# Adafruit_DC_Stepper_Wing.net
KiCad netlist of a schematic drawn in EAGLE
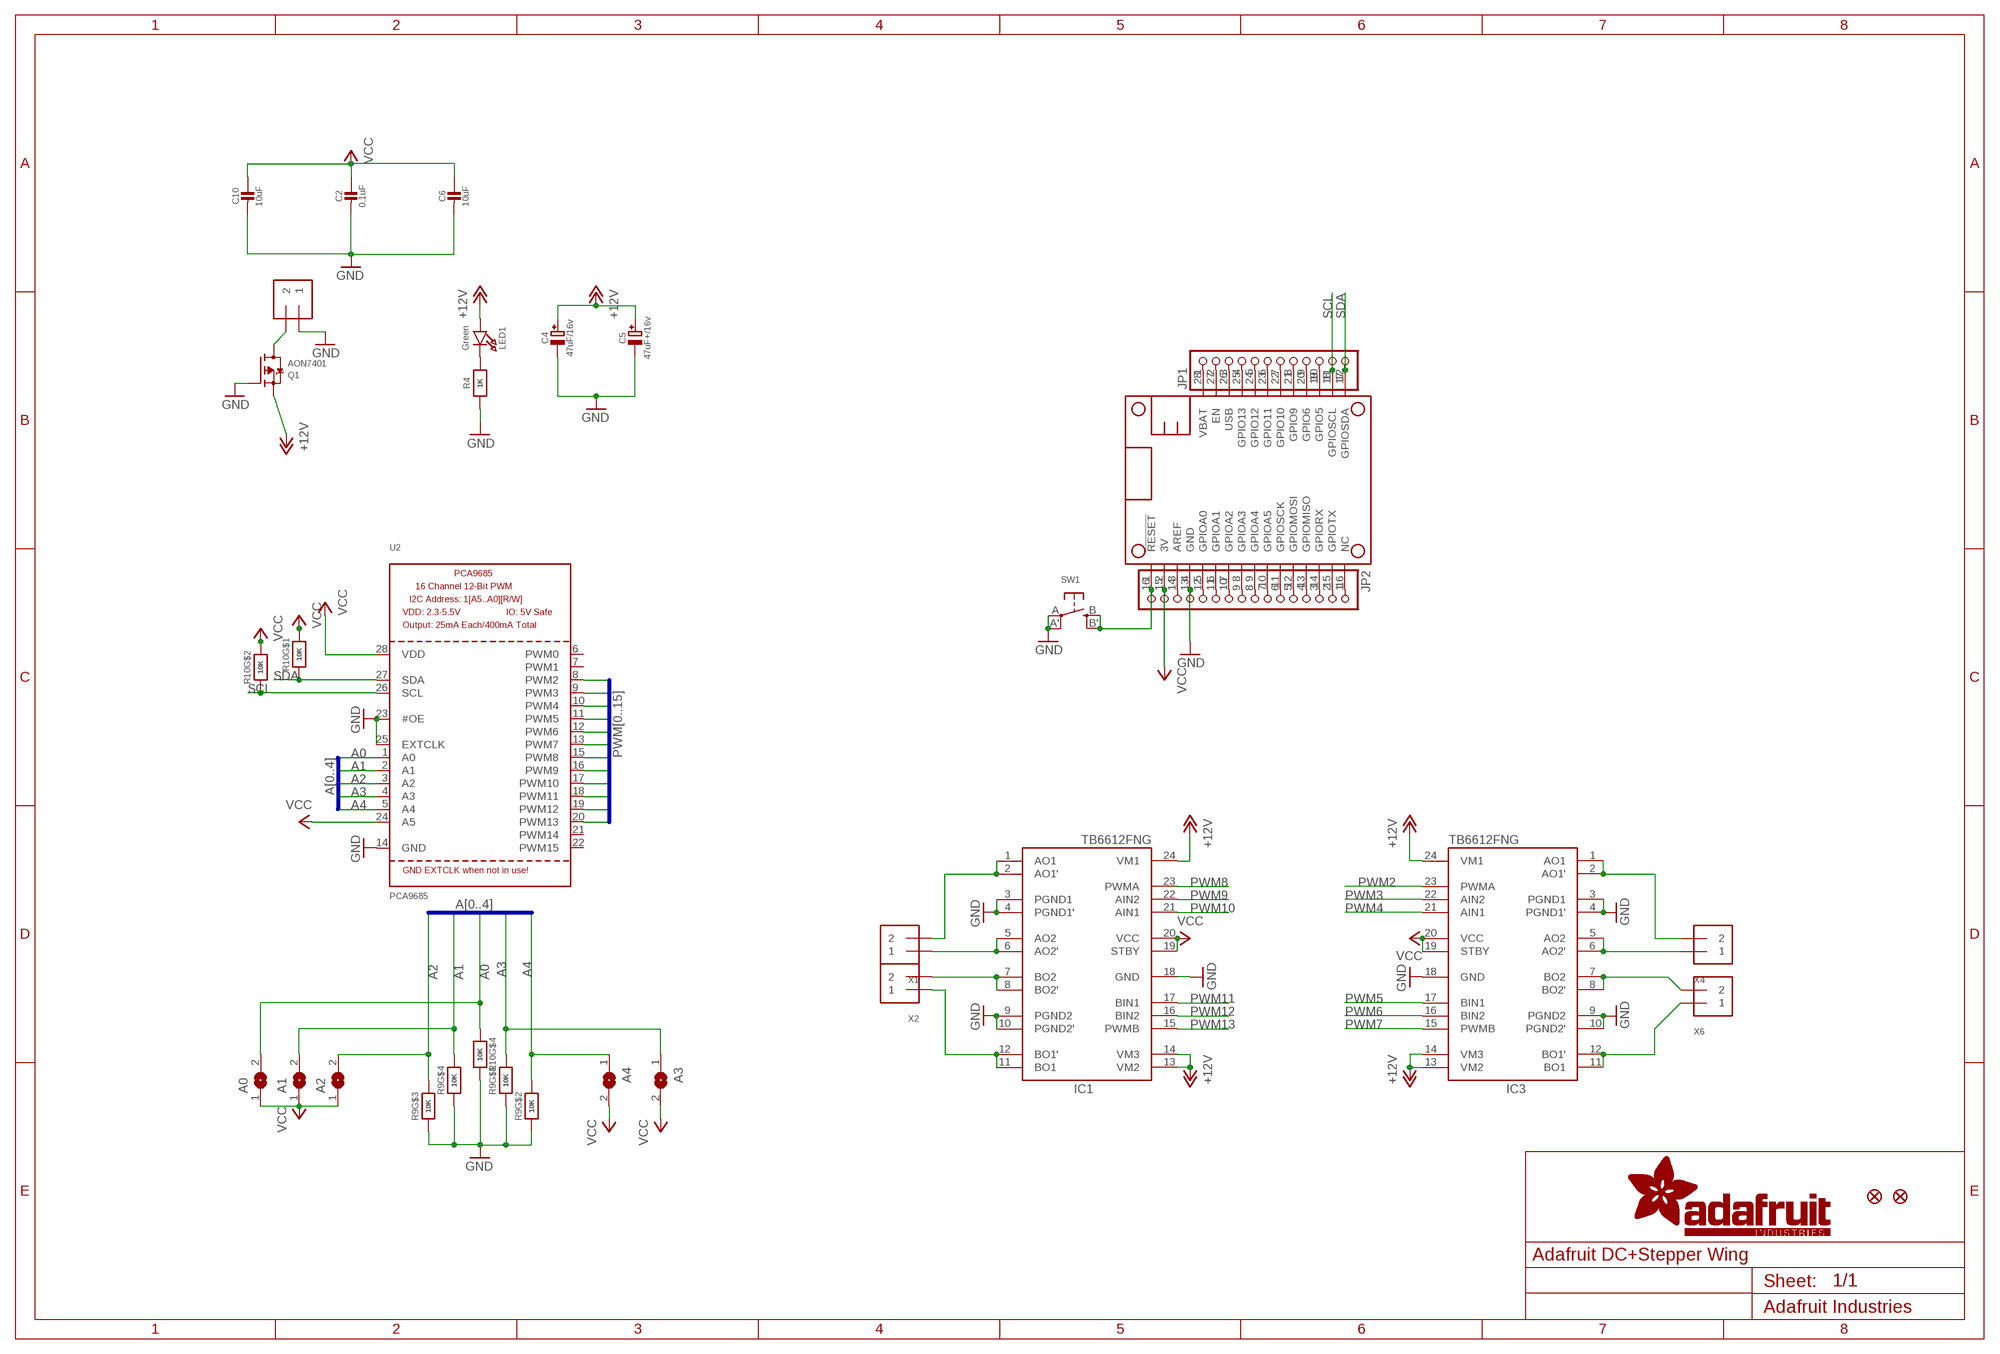
[diagram p0: schematic, sheet 1]

(export (version "E")
  (design (tool "Eeschema 10.0.6"))
  (components
    (comp (ref "A0")
      (value "SOLDERJUMPERREFLOW_NOPASTE")
      (footprint "eagle-import:SOLDERJUMPER_REFLOW_NOPASTE")
      (libsource (lib "eagle-import") (part "SOLDERJUMPERREFLOW_NOPASTE"))
    )
    (comp (ref "A1")
      (value "SOLDERJUMPERREFLOW_NOPASTE")
      (footprint "eagle-import:SOLDERJUMPER_REFLOW_NOPASTE")
      (libsource (lib "eagle-import") (part "SOLDERJUMPERREFLOW_NOPASTE"))
    )
    (comp (ref "A2")
      (value "SOLDERJUMPERREFLOW_NOPASTE")
      (footprint "eagle-import:SOLDERJUMPER_REFLOW_NOPASTE")
      (libsource (lib "eagle-import") (part "SOLDERJUMPERREFLOW_NOPASTE"))
    )
    (comp (ref "A3")
      (value "SOLDERJUMPERREFLOW_NOPASTE")
      (footprint "eagle-import:SOLDERJUMPER_REFLOW_NOPASTE")
      (libsource (lib "eagle-import") (part "SOLDERJUMPERREFLOW_NOPASTE"))
    )
    (comp (ref "A4")
      (value "SOLDERJUMPERREFLOW_NOPASTE")
      (footprint "eagle-import:SOLDERJUMPER_REFLOW_NOPASTE")
      (libsource (lib "eagle-import") (part "SOLDERJUMPERREFLOW_NOPASTE"))
    )
    (comp (ref "C2")
      (value "0.1uF")
      (footprint "eagle-import:0805-NO")
      (libsource (lib "eagle-import") (part "CAP_CERAMIC0805-NOOUTLINE"))
    )
    (comp (ref "C4")
      (value "47uF/16v")
      (footprint "eagle-import:PANASONIC_C")
      (libsource (lib "eagle-import") (part "CAP_ELECTROLYTICPANASONIC_C"))
    )
    (comp (ref "C5")
      (value "47uF+/16v")
      (footprint "eagle-import:PANASONIC_C")
      (libsource (lib "eagle-import") (part "CAP_ELECTROLYTICPANASONIC_C"))
    )
    (comp (ref "C6")
      (value "10uF")
      (footprint "eagle-import:0805-NO")
      (libsource (lib "eagle-import") (part "CAP_CERAMIC0805-NOOUTLINE"))
    )
    (comp (ref "C10")
      (value "10uF")
      (footprint "eagle-import:0805-NO")
      (libsource (lib "eagle-import") (part "CAP_CERAMIC0805-NOOUTLINE"))
    )
    (comp (ref "IC1")
      (value "TB6612FNG")
      (footprint "eagle-import:SSOP24")
      (libsource (lib "eagle-import") (part "TB6612FNG"))
    )
    (comp (ref "IC3")
      (value "TB6612FNG")
      (footprint "eagle-import:SSOP24")
      (libsource (lib "eagle-import") (part "TB6612FNG"))
    )
    (comp (ref "JP1")
      (value "HEADER-1X12")
      (footprint "eagle-import:1X12_ROUND")
      (libsource (lib "eagle-import") (part "HEADER-1X12"))
    )
    (comp (ref "JP2")
      (value "HEADER-1X16ROUND")
      (footprint "eagle-import:1X16_ROUND")
      (libsource (lib "eagle-import") (part "HEADER-1X16ROUND"))
    )
    (comp (ref "LED1")
      (value "Green")
      (footprint "eagle-import:CHIPLED_0805_NOOUTLINE")
      (libsource (lib "eagle-import") (part "LED0805_NOOUTLINE"))
    )
    (comp (ref "MPOWER")
      (value "1X2-3.5MM")
      (footprint "eagle-import:1X2-3.5MM")
      (libsource (lib "eagle-import") (part "1X2-3.5MM"))
    )
    (comp (ref "MS1")
      (value "FEATHERWING")
      (footprint "eagle-import:FEATHERWING")
      (libsource (lib "eagle-import") (part "FEATHERWING"))
    )
    (comp (ref "Q1")
      (value "AON7401")
      (footprint "eagle-import:POWERDI3333")
      (libsource (lib "eagle-import") (part "MOSFET-P-POWERDI3333"))
    )
    (comp (ref "R4")
      (value "1K")
      (footprint "eagle-import:0805-NO")
      (libsource (lib "eagle-import") (part "RESISTOR0805_NOOUTLINE"))
    )
    (comp (ref "R9")
      (value "10K")
      (footprint "eagle-import:RESPACK_4X0603")
      (libsource (lib "eagle-import") (part "RESISTOR_4PACK"))
    )
    (comp (ref "R10")
      (value "10K")
      (footprint "eagle-import:RESPACK_4X0603")
      (libsource (lib "eagle-import") (part "RESISTOR_4PACK"))
    )
    (comp (ref "SW1")
      (value "SWITCH_TACT_SMT4.6X2.8")
      (footprint "eagle-import:BTN_KMR2_4.6X2.8")
      (libsource (lib "eagle-import") (part "SWITCH_TACT_SMT4.6X2.8"))
    )
    (comp (ref "U$3")
      (value "FIDUCIAL\"\"")
      (footprint "eagle-import:FIDUCIAL_1MM")
      (libsource (lib "eagle-import") (part "FIDUCIAL{dblquote}{dblquote}"))
    )
    (comp (ref "U$4")
      (value "FIDUCIAL\"\"")
      (footprint "eagle-import:FIDUCIAL_1MM")
      (libsource (lib "eagle-import") (part "FIDUCIAL{dblquote}{dblquote}"))
    )
    (comp (ref "U2")
      (value "PCA9685")
      (footprint "eagle-import:TSSOP28")
      (libsource (lib "eagle-import") (part "PCA9685"))
    )
    (comp (ref "X1")
      (value "TERMBLOCK_1X2")
      (footprint "eagle-import:TERMBLOCK_1X2-3.5MM")
      (libsource (lib "eagle-import") (part "TERMBLOCK_1X2"))
    )
    (comp (ref "X2")
      (value "TERMBLOCK_1X2")
      (footprint "eagle-import:TERMBLOCK_1X2-3.5MM")
      (libsource (lib "eagle-import") (part "TERMBLOCK_1X2"))
    )
    (comp (ref "X4")
      (value "TERMBLOCK_1X2")
      (footprint "eagle-import:TERMBLOCK_1X2-3.5MM")
      (libsource (lib "eagle-import") (part "TERMBLOCK_1X2"))
    )
    (comp (ref "X6")
      (value "TERMBLOCK_1X2")
      (footprint "eagle-import:TERMBLOCK_1X2-3.5MM")
      (libsource (lib "eagle-import") (part "TERMBLOCK_1X2"))
    )
  )
  (nets
    (net (code "5") (name "+12V") (class "Default")
      (node (ref "C4") (pin "+") (pinfunction "+_+") (pintype "passive"))
      (node (ref "C5") (pin "+") (pinfunction "+_+") (pintype "passive"))
      (node (ref "IC1") (pin "13") (pinfunction "VM2_13") (pintype "power_in"))
      (node (ref "IC1") (pin "14") (pinfunction "VM3_14") (pintype "power_in"))
      (node (ref "IC1") (pin "24") (pinfunction "VM1_24") (pintype "power_in"))
      (node (ref "IC3") (pin "13") (pinfunction "VM2_13") (pintype "power_in"))
      (node (ref "IC3") (pin "14") (pinfunction "VM3_14") (pintype "power_in"))
      (node (ref "IC3") (pin "24") (pinfunction "VM1_24") (pintype "power_in"))
      (node (ref "LED1") (pin "A") (pinfunction "A_A") (pintype "passive"))
      (node (ref "Q1") (pin "1") (pinfunction "S_1") (pintype "passive"))
      (node (ref "Q1") (pin "2") (pinfunction "S_2") (pintype "passive"))
      (node (ref "Q1") (pin "3") (pinfunction "S_3") (pintype "passive"))
    )
    (net (code "6") (name "/A0") (class "Default")
      (node (ref "A0") (pin "2") (pinfunction "2_2") (pintype "passive"))
      (node (ref "R10") (pin "4") (pinfunction "1_4") (pintype "passive"))
      (node (ref "U2") (pin "1") (pinfunction "A0_1") (pintype "bidirectional"))
    )
    (net (code "7") (name "/A1") (class "Default")
      (node (ref "A1") (pin "2") (pinfunction "2_2") (pintype "passive"))
      (node (ref "R9") (pin "5") (pinfunction "2_5") (pintype "passive"))
      (node (ref "U2") (pin "2") (pinfunction "A1_2") (pintype "bidirectional"))
    )
    (net (code "8") (name "/A2") (class "Default")
      (node (ref "A2") (pin "2") (pinfunction "2_2") (pintype "passive"))
      (node (ref "R9") (pin "6") (pinfunction "2_6") (pintype "passive"))
      (node (ref "U2") (pin "3") (pinfunction "A2_3") (pintype "bidirectional"))
    )
    (net (code "9") (name "/A3") (class "Default")
      (node (ref "A3") (pin "1") (pinfunction "1_1") (pintype "passive"))
      (node (ref "R9") (pin "8") (pinfunction "2_8") (pintype "passive"))
      (node (ref "U2") (pin "4") (pinfunction "A3_4") (pintype "bidirectional"))
    )
    (net (code "10") (name "/A4") (class "Default")
      (node (ref "A4") (pin "1") (pinfunction "1_1") (pintype "passive"))
      (node (ref "R9") (pin "7") (pinfunction "2_7") (pintype "passive"))
      (node (ref "U2") (pin "5") (pinfunction "A4_5") (pintype "bidirectional"))
    )
    (net (code "12") (name "/PWM2") (class "Default")
      (node (ref "IC3") (pin "23") (pinfunction "PWMA_23") (pintype "input"))
      (node (ref "U2") (pin "8") (pinfunction "PWM2_8") (pintype "output"))
    )
    (net (code "13") (name "/PWM3") (class "Default")
      (node (ref "IC3") (pin "22") (pinfunction "AIN2_22") (pintype "input"))
      (node (ref "U2") (pin "9") (pinfunction "PWM3_9") (pintype "output"))
    )
    (net (code "14") (name "/PWM4") (class "Default")
      (node (ref "IC3") (pin "21") (pinfunction "AIN1_21") (pintype "input"))
      (node (ref "U2") (pin "10") (pinfunction "PWM4_10") (pintype "output"))
    )
    (net (code "15") (name "/PWM5") (class "Default")
      (node (ref "IC3") (pin "17") (pinfunction "BIN1_17") (pintype "input"))
      (node (ref "U2") (pin "11") (pinfunction "PWM5_11") (pintype "output"))
    )
    (net (code "16") (name "/PWM6") (class "Default")
      (node (ref "IC3") (pin "16") (pinfunction "BIN2_16") (pintype "input"))
      (node (ref "U2") (pin "12") (pinfunction "PWM6_12") (pintype "output"))
    )
    (net (code "17") (name "/PWM7") (class "Default")
      (node (ref "IC3") (pin "15") (pinfunction "PWMB_15") (pintype "input"))
      (node (ref "U2") (pin "13") (pinfunction "PWM7_13") (pintype "output"))
    )
    (net (code "18") (name "/PWM8") (class "Default")
      (node (ref "IC1") (pin "23") (pinfunction "PWMA_23") (pintype "input"))
      (node (ref "U2") (pin "15") (pinfunction "PWM8_15") (pintype "output"))
    )
    (net (code "19") (name "/PWM9") (class "Default")
      (node (ref "IC1") (pin "22") (pinfunction "AIN2_22") (pintype "input"))
      (node (ref "U2") (pin "16") (pinfunction "PWM9_16") (pintype "output"))
    )
    (net (code "20") (name "/PWM10") (class "Default")
      (node (ref "IC1") (pin "21") (pinfunction "AIN1_21") (pintype "input"))
      (node (ref "U2") (pin "17") (pinfunction "PWM10_17") (pintype "output"))
    )
    (net (code "21") (name "/PWM11") (class "Default")
      (node (ref "IC1") (pin "17") (pinfunction "BIN1_17") (pintype "input"))
      (node (ref "U2") (pin "18") (pinfunction "PWM11_18") (pintype "output"))
    )
    (net (code "22") (name "/PWM12") (class "Default")
      (node (ref "IC1") (pin "16") (pinfunction "BIN2_16") (pintype "input"))
      (node (ref "U2") (pin "19") (pinfunction "PWM12_19") (pintype "output"))
    )
    (net (code "23") (name "/PWM13") (class "Default")
      (node (ref "IC1") (pin "15") (pinfunction "PWMB_15") (pintype "input"))
      (node (ref "U2") (pin "20") (pinfunction "PWM13_20") (pintype "output"))
    )
    (net (code "25") (name "/SCL") (class "Default")
      (node (ref "JP1") (pin "11") (pinfunction "11_11") (pintype "passive"))
      (node (ref "MS1") (pin "18") (pinfunction "GPIOSCL_18") (pintype "bidirectional"))
      (node (ref "R10") (pin "2") (pinfunction "1_2") (pintype "passive"))
      (node (ref "U2") (pin "26") (pinfunction "SCL_26") (pintype "bidirectional"))
    )
    (net (code "26") (name "/SDA") (class "Default")
      (node (ref "JP1") (pin "12") (pinfunction "12_12") (pintype "passive"))
      (node (ref "MS1") (pin "17") (pinfunction "GPIOSDA_17") (pintype "bidirectional"))
      (node (ref "R10") (pin "1") (pinfunction "1_1") (pintype "passive"))
      (node (ref "U2") (pin "27") (pinfunction "SDA_27") (pintype "bidirectional"))
    )
    (net (code "27") (name "GND") (class "Default")
      (node (ref "C10") (pin "2") (pinfunction "2_2") (pintype "passive"))
      (node (ref "C2") (pin "2") (pinfunction "2_2") (pintype "passive"))
      (node (ref "C4") (pin "-") (pinfunction "-_-") (pintype "passive"))
      (node (ref "C5") (pin "-") (pinfunction "-_-") (pintype "passive"))
      (node (ref "C6") (pin "2") (pinfunction "2_2") (pintype "passive"))
      (node (ref "IC1") (pin "10") (pinfunction "PGND2'_10") (pintype "power_in"))
      (node (ref "IC1") (pin "18") (pinfunction "GND_18") (pintype "power_in"))
      (node (ref "IC1") (pin "3") (pinfunction "PGND1_3") (pintype "power_in"))
      (node (ref "IC1") (pin "4") (pinfunction "PGND1'_4") (pintype "power_in"))
      (node (ref "IC1") (pin "9") (pinfunction "PGND2_9") (pintype "power_in"))
      (node (ref "IC3") (pin "10") (pinfunction "PGND2'_10") (pintype "power_in"))
      (node (ref "IC3") (pin "18") (pinfunction "GND_18") (pintype "power_in"))
      (node (ref "IC3") (pin "3") (pinfunction "PGND1_3") (pintype "power_in"))
      (node (ref "IC3") (pin "4") (pinfunction "PGND1'_4") (pintype "power_in"))
      (node (ref "IC3") (pin "9") (pinfunction "PGND2_9") (pintype "power_in"))
      (node (ref "JP2") (pin "13") (pinfunction "13_13") (pintype "passive"))
      (node (ref "MPOWER") (pin "1") (pinfunction "1_1") (pintype "passive"))
      (node (ref "MS1") (pin "4") (pinfunction "GND_4") (pintype "power_in"))
      (node (ref "Q1") (pin "4") (pinfunction "G_4") (pintype "passive"))
      (node (ref "R10") (pin "5") (pinfunction "2_5") (pintype "passive"))
      (node (ref "R4") (pin "1") (pinfunction "1_1") (pintype "passive"))
      (node (ref "R9") (pin "1") (pinfunction "1_1") (pintype "passive"))
      (node (ref "R9") (pin "2") (pinfunction "1_2") (pintype "passive"))
      (node (ref "R9") (pin "3") (pinfunction "1_3") (pintype "passive"))
      (node (ref "R9") (pin "4") (pinfunction "1_4") (pintype "passive"))
      (node (ref "SW1") (pin "A") (pinfunction "P_A") (pintype "passive"))
      (node (ref "SW1") (pin "A'") (pinfunction "P1_A'") (pintype "passive"))
      (node (ref "U2") (pin "14") (pinfunction "GND_14") (pintype "power_in"))
      (node (ref "U2") (pin "23") (pinfunction "#OE_23") (pintype "input"))
      (node (ref "U2") (pin "25") (pinfunction "EXTCLK_25") (pintype "input"))
    )
    (net (code "28") (name "Net-(IC1-AO1')") (class "Default")
      (node (ref "IC1") (pin "1") (pinfunction "AO1_1") (pintype "output"))
      (node (ref "IC1") (pin "2") (pinfunction "AO1'_2") (pintype "output"))
      (node (ref "X1") (pin "2") (pinfunction "2_2") (pintype "passive"))
    )
    (net (code "29") (name "Net-(IC1-AO2')") (class "Default")
      (node (ref "IC1") (pin "5") (pinfunction "AO2_5") (pintype "output"))
      (node (ref "IC1") (pin "6") (pinfunction "AO2'_6") (pintype "output"))
      (node (ref "X1") (pin "1") (pinfunction "1_1") (pintype "passive"))
    )
    (net (code "30") (name "Net-(IC1-BO1')") (class "Default")
      (node (ref "IC1") (pin "11") (pinfunction "BO1_11") (pintype "output"))
      (node (ref "IC1") (pin "12") (pinfunction "BO1'_12") (pintype "output"))
      (node (ref "X2") (pin "1") (pinfunction "1_1") (pintype "passive"))
    )
    (net (code "31") (name "Net-(IC1-BO2')") (class "Default")
      (node (ref "IC1") (pin "7") (pinfunction "BO2_7") (pintype "output"))
      (node (ref "IC1") (pin "8") (pinfunction "BO2'_8") (pintype "output"))
      (node (ref "X2") (pin "2") (pinfunction "2_2") (pintype "passive"))
    )
    (net (code "32") (name "Net-(IC3-AO1')") (class "Default")
      (node (ref "IC3") (pin "1") (pinfunction "AO1_1") (pintype "output"))
      (node (ref "IC3") (pin "2") (pinfunction "AO1'_2") (pintype "output"))
      (node (ref "X4") (pin "2") (pinfunction "2_2") (pintype "passive"))
    )
    (net (code "33") (name "Net-(IC3-AO2')") (class "Default")
      (node (ref "IC3") (pin "5") (pinfunction "AO2_5") (pintype "output"))
      (node (ref "IC3") (pin "6") (pinfunction "AO2'_6") (pintype "output"))
      (node (ref "X4") (pin "1") (pinfunction "1_1") (pintype "passive"))
    )
    (net (code "34") (name "Net-(IC3-BO1')") (class "Default")
      (node (ref "IC3") (pin "11") (pinfunction "BO1_11") (pintype "output"))
      (node (ref "IC3") (pin "12") (pinfunction "BO1'_12") (pintype "output"))
      (node (ref "X6") (pin "1") (pinfunction "1_1") (pintype "passive"))
    )
    (net (code "35") (name "Net-(IC3-BO2')") (class "Default")
      (node (ref "IC3") (pin "7") (pinfunction "BO2_7") (pintype "output"))
      (node (ref "IC3") (pin "8") (pinfunction "BO2'_8") (pintype "output"))
      (node (ref "X6") (pin "2") (pinfunction "2_2") (pintype "passive"))
    )
    (net (code "36") (name "Net-(LED1-PadC)") (class "Default")
      (node (ref "LED1") (pin "C") (pinfunction "C_C") (pintype "passive"))
      (node (ref "R4") (pin "2") (pinfunction "2_2") (pintype "passive"))
    )
    (net (code "37") (name "Net-(MS1-AREF)") (class "Default")
      (node (ref "JP2") (pin "14") (pinfunction "14_14") (pintype "passive"))
      (node (ref "MS1") (pin "3") (pinfunction "AREF_3") (pintype "passive"))
    )
    (net (code "38") (name "Net-(MS1-EN)") (class "Default")
      (node (ref "JP1") (pin "2") (pinfunction "2_2") (pintype "passive"))
      (node (ref "MS1") (pin "27") (pinfunction "EN_27") (pintype "passive"))
    )
    (net (code "39") (name "Net-(MS1-GPIO5)") (class "Default")
      (node (ref "JP1") (pin "10") (pinfunction "10_10") (pintype "passive"))
      (node (ref "MS1") (pin "19") (pinfunction "GPIO5_19") (pintype "bidirectional"))
    )
    (net (code "40") (name "Net-(MS1-GPIO6)") (class "Default")
      (node (ref "JP1") (pin "9") (pinfunction "9_9") (pintype "passive"))
      (node (ref "MS1") (pin "20") (pinfunction "GPIO6_20") (pintype "bidirectional"))
    )
    (net (code "41") (name "Net-(MS1-GPIO9)") (class "Default")
      (node (ref "JP1") (pin "8") (pinfunction "8_8") (pintype "passive"))
      (node (ref "MS1") (pin "21") (pinfunction "GPIO9_21") (pintype "bidirectional"))
    )
    (net (code "42") (name "Net-(MS1-GPIO10)") (class "Default")
      (node (ref "JP1") (pin "7") (pinfunction "7_7") (pintype "passive"))
      (node (ref "MS1") (pin "22") (pinfunction "GPIO10_22") (pintype "bidirectional"))
    )
    (net (code "43") (name "Net-(MS1-GPIO11)") (class "Default")
      (node (ref "JP1") (pin "6") (pinfunction "6_6") (pintype "passive"))
      (node (ref "MS1") (pin "23") (pinfunction "GPIO11_23") (pintype "bidirectional"))
    )
    (net (code "44") (name "Net-(MS1-GPIO12)") (class "Default")
      (node (ref "JP1") (pin "5") (pinfunction "5_5") (pintype "passive"))
      (node (ref "MS1") (pin "24") (pinfunction "GPIO12_24") (pintype "bidirectional"))
    )
    (net (code "45") (name "Net-(MS1-GPIO13)") (class "Default")
      (node (ref "JP1") (pin "4") (pinfunction "4_4") (pintype "passive"))
      (node (ref "MS1") (pin "25") (pinfunction "GPIO13_25") (pintype "bidirectional"))
    )
    (net (code "46") (name "Net-(MS1-GPIOA0)") (class "Default")
      (node (ref "JP2") (pin "12") (pinfunction "12_12") (pintype "passive"))
      (node (ref "MS1") (pin "5") (pinfunction "GPIOA0_5") (pintype "bidirectional"))
    )
    (net (code "47") (name "Net-(MS1-GPIOA1)") (class "Default")
      (node (ref "JP2") (pin "11") (pinfunction "11_11") (pintype "passive"))
      (node (ref "MS1") (pin "6") (pinfunction "GPIOA1_6") (pintype "bidirectional"))
    )
    (net (code "48") (name "Net-(MS1-GPIOA2)") (class "Default")
      (node (ref "JP2") (pin "10") (pinfunction "10_10") (pintype "passive"))
      (node (ref "MS1") (pin "7") (pinfunction "GPIOA2_7") (pintype "bidirectional"))
    )
    (net (code "49") (name "Net-(MS1-GPIOA3)") (class "Default")
      (node (ref "JP2") (pin "9") (pinfunction "9_9") (pintype "passive"))
      (node (ref "MS1") (pin "8") (pinfunction "GPIOA3_8") (pintype "bidirectional"))
    )
    (net (code "50") (name "Net-(MS1-GPIOA4)") (class "Default")
      (node (ref "JP2") (pin "8") (pinfunction "8_8") (pintype "passive"))
      (node (ref "MS1") (pin "9") (pinfunction "GPIOA4_9") (pintype "bidirectional"))
    )
    (net (code "51") (name "Net-(MS1-GPIOA5)") (class "Default")
      (node (ref "JP2") (pin "7") (pinfunction "7_7") (pintype "passive"))
      (node (ref "MS1") (pin "10") (pinfunction "GPIOA5_10") (pintype "bidirectional"))
    )
    (net (code "52") (name "Net-(MS1-GPIOMISO)") (class "Default")
      (node (ref "JP2") (pin "4") (pinfunction "4_4") (pintype "passive"))
      (node (ref "MS1") (pin "13") (pinfunction "GPIOMISO_13") (pintype "bidirectional"))
    )
    (net (code "53") (name "Net-(MS1-GPIOMOSI)") (class "Default")
      (node (ref "JP2") (pin "5") (pinfunction "5_5") (pintype "passive"))
      (node (ref "MS1") (pin "12") (pinfunction "GPIOMOSI_12") (pintype "bidirectional"))
    )
    (net (code "54") (name "Net-(MS1-GPIORX)") (class "Default")
      (node (ref "JP2") (pin "3") (pinfunction "3_3") (pintype "passive"))
      (node (ref "MS1") (pin "14") (pinfunction "GPIORX_14") (pintype "bidirectional"))
    )
    (net (code "55") (name "Net-(MS1-GPIOSCK)") (class "Default")
      (node (ref "JP2") (pin "6") (pinfunction "6_6") (pintype "passive"))
      (node (ref "MS1") (pin "11") (pinfunction "GPIOSCK_11") (pintype "bidirectional"))
    )
    (net (code "56") (name "Net-(MS1-GPIOTX)") (class "Default")
      (node (ref "JP2") (pin "2") (pinfunction "2_2") (pintype "passive"))
      (node (ref "MS1") (pin "15") (pinfunction "GPIOTX_15") (pintype "bidirectional"))
    )
    (net (code "57") (name "Net-(MS1-NC)") (class "Default")
      (node (ref "JP2") (pin "1") (pinfunction "1_1") (pintype "passive"))
      (node (ref "MS1") (pin "16") (pinfunction "NC_16") (pintype "passive"))
    )
    (net (code "58") (name "Net-(MS1-USB)") (class "Default")
      (node (ref "JP1") (pin "3") (pinfunction "3_3") (pintype "passive"))
      (node (ref "MS1") (pin "26") (pinfunction "USB_26") (pintype "power_in"))
    )
    (net (code "59") (name "Net-(MS1-VBAT)") (class "Default")
      (node (ref "JP1") (pin "1") (pinfunction "1_1") (pintype "passive"))
      (node (ref "MS1") (pin "28") (pinfunction "VBAT_28") (pintype "power_in"))
    )
    (net (code "60") (name "Net-(MS1-~{RESET})") (class "Default")
      (node (ref "JP2") (pin "16") (pinfunction "16_16") (pintype "passive"))
      (node (ref "MS1") (pin "1") (pinfunction "~{RESET}_1") (pintype "input"))
      (node (ref "SW1") (pin "B") (pinfunction "S_B") (pintype "passive"))
      (node (ref "SW1") (pin "B'") (pinfunction "S1_B'") (pintype "passive"))
    )
    (net (code "61") (name "Net-(Q1-D)") (class "Default")
      (node (ref "MPOWER") (pin "2") (pinfunction "2_2") (pintype "passive"))
      (node (ref "Q1") (pin "5678") (pinfunction "D_5678") (pintype "passive"))
    )
    (net (code "62") (name "VCC") (class "Default")
      (node (ref "A0") (pin "1") (pinfunction "1_1") (pintype "passive"))
      (node (ref "A1") (pin "1") (pinfunction "1_1") (pintype "passive"))
      (node (ref "A2") (pin "1") (pinfunction "1_1") (pintype "passive"))
      (node (ref "A3") (pin "2") (pinfunction "2_2") (pintype "passive"))
      (node (ref "A4") (pin "2") (pinfunction "2_2") (pintype "passive"))
      (node (ref "C10") (pin "1") (pinfunction "1_1") (pintype "passive"))
      (node (ref "C2") (pin "1") (pinfunction "1_1") (pintype "passive"))
      (node (ref "C6") (pin "1") (pinfunction "1_1") (pintype "passive"))
      (node (ref "IC1") (pin "19") (pinfunction "STBY_19") (pintype "input"))
      (node (ref "IC1") (pin "20") (pinfunction "VCC_20") (pintype "power_in"))
      (node (ref "IC3") (pin "19") (pinfunction "STBY_19") (pintype "input"))
      (node (ref "IC3") (pin "20") (pinfunction "VCC_20") (pintype "power_in"))
      (node (ref "JP2") (pin "15") (pinfunction "15_15") (pintype "passive"))
      (node (ref "MS1") (pin "2") (pinfunction "3V_2") (pintype "power_in"))
      (node (ref "R10") (pin "7") (pinfunction "2_7") (pintype "passive"))
      (node (ref "R10") (pin "8") (pinfunction "2_8") (pintype "passive"))
      (node (ref "U2") (pin "24") (pinfunction "A5_24") (pintype "bidirectional"))
      (node (ref "U2") (pin "28") (pinfunction "VDD_28") (pintype "power_in"))
    )
    (net (code "63") (name "unconnected-(U2-PWM0-Pad6)") (class "Default")
      (node (ref "U2") (pin "6") (pinfunction "PWM0_6") (pintype "output"))
    )
    (net (code "64") (name "unconnected-(U2-PWM1-Pad7)") (class "Default")
      (node (ref "U2") (pin "7") (pinfunction "PWM1_7") (pintype "output"))
    )
    (net (code "65") (name "unconnected-(U2-PWM14-Pad21)") (class "Default")
      (node (ref "U2") (pin "21") (pinfunction "PWM14_21") (pintype "output"))
    )
    (net (code "66") (name "unconnected-(U2-PWM15-Pad22)") (class "Default")
      (node (ref "U2") (pin "22") (pinfunction "PWM15_22") (pintype "output"))
    )
  )
)
